# onStep-board-power.net
KiCad netlist of a schematic drawn in Altium Designer
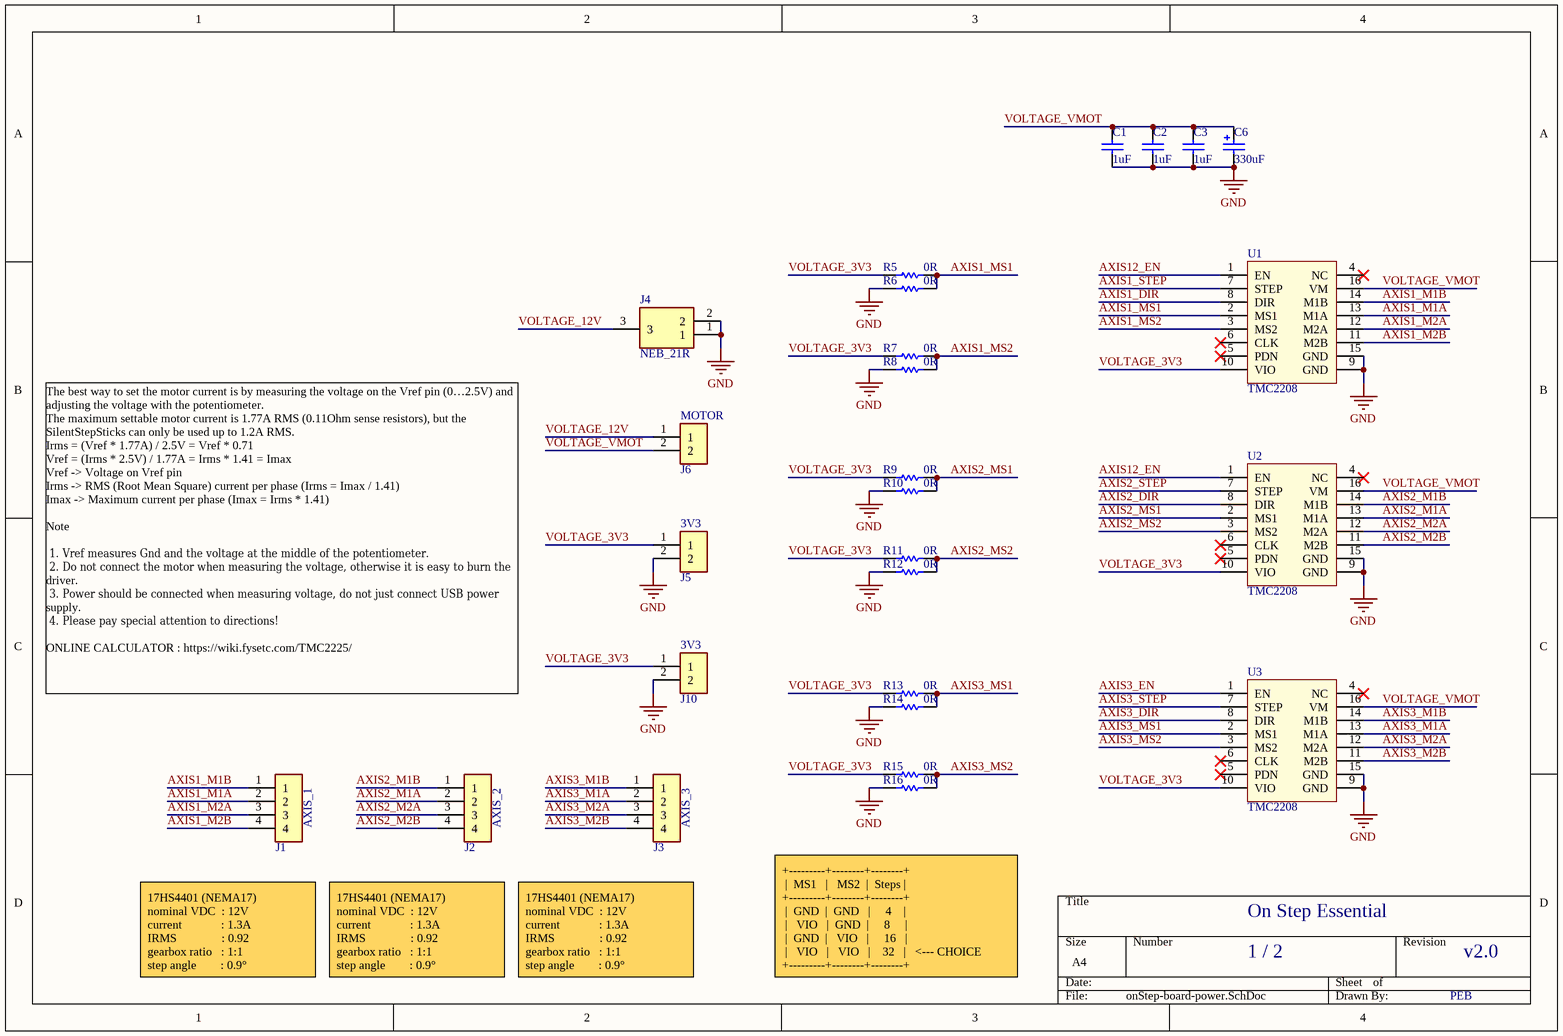
[diagram p0: onStep-board-power.SchDoc]

(export (version "E")
  (design (tool "Eeschema 10.0.6"))
  (components
    (comp (ref "C1")
      (value "1uF")
      (footprint "0805")
      (description "Capacitor")
      (fields (field (name "Comment") "Cap") (field (name "PUBLISHER") "Altium Limited"))
      (libsource (lib "Miscellaneous Devices") (part "Cap"))
    )
    (comp (ref "C2")
      (value "1uF")
      (footprint "0805")
      (description "Capacitor")
      (fields (field (name "Comment") "Cap") (field (name "PUBLISHER") "Altium Limited"))
      (libsource (lib "Miscellaneous Devices") (part "Cap"))
    )
    (comp (ref "C3")
      (value "1uF")
      (footprint "0805")
      (description "Capacitor")
      (fields (field (name "Comment") "Cap") (field (name "PUBLISHER") "Altium Limited"))
      (libsource (lib "Miscellaneous Devices") (part "Cap"))
    )
    (comp (ref "C6")
      (value "330uF")
      (footprint "WCAP-ASLL_8x10.5")
      (description "WCAP-ASLL Aluminum Electrolytic Capacitors, size Ф8x10.5mm, 25V DC, 330uF")
      (fields (field (name "PART NUMBER") "865060453008") (field (name "PUBLISHER") "Wurth Elektronik"))
      (libsource (lib "ALTIUM-WCAP-ASLL-rev17a") (part "865060453008"))
    )
    (comp (ref "J1")
      (value "AXIS_1")
      (footprint "lib_common:B4BXHALFSN")
      (description "Connector")
      (fields (field (name "MANUFACTURER_PART_NUMBER") "B4B-XH-A(LF)(SN)"))
      (libsource (lib "lib_common") (part "B4B-XH-A_LF__SN_"))
    )
    (comp (ref "J2")
      (value "AXIS_2")
      (footprint "lib_common:B4BXHALFSN")
      (description "Connector")
      (fields (field (name "MANUFACTURER_PART_NUMBER") "B4B-XH-A(LF)(SN)"))
      (libsource (lib "lib_common") (part "B4B-XH-A_LF__SN_"))
    )
    (comp (ref "J3")
      (value "AXIS_3")
      (footprint "lib_common:B4BXHALFSN")
      (description "Connector")
      (fields (field (name "MANUFACTURER_PART_NUMBER") "B4B-XH-A(LF)(SN)"))
      (libsource (lib "lib_common") (part "B4B-XH-A_LF__SN_"))
    )
    (comp (ref "J4")
      (value "NEB_21R")
      (footprint "lib_common:NEB21R")
      (description "Connector")
      (fields (field (name "MANUFACTURER_PART_NUMBER") "NEB+21+R"))
      (libsource (lib "lib_common") (part "NEB_21R"))
    )
    (comp (ref "J5")
      (value "3V3")
      (footprint "B2BXHALFSN")
      (description "Connector")
      (fields (field (name "MANUFACTURER_PART_NUMBER") "B2B-XH-A(LF)(SN)"))
      (libsource (lib "lib_common") (part "B2B-XH-A_LF__SN_"))
    )
    (comp (ref "J6")
      (value "MOTOR")
      (footprint "lib_common:B2BXHALFSN")
      (description "Connector")
      (fields (field (name "MANUFACTURER_PART_NUMBER") "B2B-XH-A(LF)(SN)"))
      (libsource (lib "lib_common") (part "B2B-XH-A_LF__SN_"))
    )
    (comp (ref "J10")
      (value "3V3")
      (footprint "B2BXHALFSN")
      (description "Connector")
      (fields (field (name "MANUFACTURER_PART_NUMBER") "B2B-XH-A(LF)(SN)"))
      (libsource (lib "lib_common") (part "B2B-XH-A_LF__SN_"))
    )
    (comp (ref "R5")
      (value "0R")
      (footprint "0805")
      (description "Resistor")
      (fields (field (name "Comment") "Res1") (field (name "PUBLISHER") "Altium Limited"))
      (libsource (lib "Miscellaneous Devices") (part "Res1"))
    )
    (comp (ref "R6")
      (value "0R")
      (footprint "0805")
      (description "Resistor")
      (fields (field (name "Comment") "Res1") (field (name "PUBLISHER") "Altium Limited"))
      (libsource (lib "Miscellaneous Devices") (part "Res1"))
    )
    (comp (ref "R7")
      (value "0R")
      (footprint "0805")
      (description "Resistor")
      (fields (field (name "Comment") "Res1") (field (name "PUBLISHER") "Altium Limited"))
      (libsource (lib "Miscellaneous Devices") (part "Res1"))
    )
    (comp (ref "R8")
      (value "0R")
      (footprint "0805")
      (description "Resistor")
      (fields (field (name "Comment") "Res1") (field (name "PUBLISHER") "Altium Limited"))
      (libsource (lib "Miscellaneous Devices") (part "Res1"))
    )
    (comp (ref "R9")
      (value "0R")
      (footprint "0805")
      (description "Resistor")
      (fields (field (name "Comment") "Res1") (field (name "PUBLISHER") "Altium Limited"))
      (libsource (lib "Miscellaneous Devices") (part "Res1"))
    )
    (comp (ref "R10")
      (value "0R")
      (footprint "0805")
      (description "Resistor")
      (fields (field (name "Comment") "Res1") (field (name "PUBLISHER") "Altium Limited"))
      (libsource (lib "Miscellaneous Devices") (part "Res1"))
    )
    (comp (ref "R11")
      (value "0R")
      (footprint "0805")
      (description "Resistor")
      (fields (field (name "Comment") "Res1") (field (name "PUBLISHER") "Altium Limited"))
      (libsource (lib "Miscellaneous Devices") (part "Res1"))
    )
    (comp (ref "R12")
      (value "0R")
      (footprint "0805")
      (description "Resistor")
      (fields (field (name "Comment") "Res1") (field (name "PUBLISHER") "Altium Limited"))
      (libsource (lib "Miscellaneous Devices") (part "Res1"))
    )
    (comp (ref "R13")
      (value "0R")
      (footprint "0805")
      (description "Resistor")
      (fields (field (name "Comment") "Res1") (field (name "PUBLISHER") "Altium Limited"))
      (libsource (lib "Miscellaneous Devices") (part "Res1"))
    )
    (comp (ref "R14")
      (value "0R")
      (footprint "0805")
      (description "Resistor")
      (fields (field (name "Comment") "Res1") (field (name "PUBLISHER") "Altium Limited"))
      (libsource (lib "Miscellaneous Devices") (part "Res1"))
    )
    (comp (ref "R15")
      (value "0R")
      (footprint "0805")
      (description "Resistor")
      (fields (field (name "Comment") "Res1") (field (name "PUBLISHER") "Altium Limited"))
      (libsource (lib "Miscellaneous Devices") (part "Res1"))
    )
    (comp (ref "R16")
      (value "0R")
      (footprint "0805")
      (description "Resistor")
      (fields (field (name "Comment") "Res1") (field (name "PUBLISHER") "Altium Limited"))
      (libsource (lib "Miscellaneous Devices") (part "Res1"))
    )
    (comp (ref "U1") (value "TMC2208") (footprint "TMC22xx") (libsource (lib "lib_common") (part "TMC2208")))
    (comp (ref "U2") (value "TMC2208") (footprint "TMC22xx") (libsource (lib "lib_common") (part "TMC2208")))
    (comp (ref "U3") (value "TMC2208") (footprint "TMC22xx") (libsource (lib "lib_common") (part "TMC2208")))
  )
  (nets
    (net (code "1") (name "/AXIS1_DIR") (class "Default")
      (node (ref "U1") (pin "8") (pinfunction "DIR_8") (pintype "passive"))
    )
    (net (code "2") (name "/AXIS1_M1A") (class "Default")
      (node (ref "J1") (pin "2") (pinfunction "2_2") (pintype "passive"))
      (node (ref "U1") (pin "13") (pinfunction "M1A_13") (pintype "passive"))
    )
    (net (code "3") (name "/AXIS1_M1B") (class "Default")
      (node (ref "J1") (pin "1") (pinfunction "1_1") (pintype "passive"))
      (node (ref "U1") (pin "14") (pinfunction "M1B_14") (pintype "passive"))
    )
    (net (code "4") (name "/AXIS1_M2A") (class "Default")
      (node (ref "J1") (pin "3") (pinfunction "3_3") (pintype "passive"))
      (node (ref "U1") (pin "12") (pinfunction "M2A_12") (pintype "passive"))
    )
    (net (code "5") (name "/AXIS1_M2B") (class "Default")
      (node (ref "J1") (pin "4") (pinfunction "4_4") (pintype "passive"))
      (node (ref "U1") (pin "11") (pinfunction "M2B_11") (pintype "passive"))
    )
    (net (code "6") (name "/AXIS1_MS1") (class "Default")
      (node (ref "R5") (pin "2") (pinfunction "2_2") (pintype "passive"))
      (node (ref "R6") (pin "2") (pinfunction "2_2") (pintype "passive"))
      (node (ref "U1") (pin "2") (pinfunction "MS1_2") (pintype "passive"))
    )
    (net (code "7") (name "/AXIS1_MS2") (class "Default")
      (node (ref "R7") (pin "2") (pinfunction "2_2") (pintype "passive"))
      (node (ref "R8") (pin "2") (pinfunction "2_2") (pintype "passive"))
      (node (ref "U1") (pin "3") (pinfunction "MS2_3") (pintype "passive"))
    )
    (net (code "8") (name "/AXIS1_STEP") (class "Default")
      (node (ref "U1") (pin "7") (pinfunction "STEP_7") (pintype "passive"))
    )
    (net (code "9") (name "/AXIS2_DIR") (class "Default")
      (node (ref "U2") (pin "8") (pinfunction "DIR_8") (pintype "passive"))
    )
    (net (code "10") (name "/AXIS2_M1A") (class "Default")
      (node (ref "J2") (pin "2") (pinfunction "2_2") (pintype "passive"))
      (node (ref "U2") (pin "13") (pinfunction "M1A_13") (pintype "passive"))
    )
    (net (code "11") (name "/AXIS2_M1B") (class "Default")
      (node (ref "J2") (pin "1") (pinfunction "1_1") (pintype "passive"))
      (node (ref "U2") (pin "14") (pinfunction "M1B_14") (pintype "passive"))
    )
    (net (code "12") (name "/AXIS2_M2A") (class "Default")
      (node (ref "J2") (pin "3") (pinfunction "3_3") (pintype "passive"))
      (node (ref "U2") (pin "12") (pinfunction "M2A_12") (pintype "passive"))
    )
    (net (code "13") (name "/AXIS2_M2B") (class "Default")
      (node (ref "J2") (pin "4") (pinfunction "4_4") (pintype "passive"))
      (node (ref "U2") (pin "11") (pinfunction "M2B_11") (pintype "passive"))
    )
    (net (code "14") (name "/AXIS2_MS1") (class "Default")
      (node (ref "R10") (pin "2") (pinfunction "2_2") (pintype "passive"))
      (node (ref "R9") (pin "2") (pinfunction "2_2") (pintype "passive"))
      (node (ref "U2") (pin "2") (pinfunction "MS1_2") (pintype "passive"))
    )
    (net (code "15") (name "/AXIS2_MS2") (class "Default")
      (node (ref "R11") (pin "2") (pinfunction "2_2") (pintype "passive"))
      (node (ref "R12") (pin "2") (pinfunction "2_2") (pintype "passive"))
      (node (ref "U2") (pin "3") (pinfunction "MS2_3") (pintype "passive"))
    )
    (net (code "16") (name "/AXIS2_STEP") (class "Default")
      (node (ref "U2") (pin "7") (pinfunction "STEP_7") (pintype "passive"))
    )
    (net (code "17") (name "/AXIS3_DIR") (class "Default")
      (node (ref "U3") (pin "8") (pinfunction "DIR_8") (pintype "passive"))
    )
    (net (code "18") (name "/AXIS3_EN") (class "Default")
      (node (ref "U3") (pin "1") (pinfunction "EN_1") (pintype "passive"))
    )
    (net (code "19") (name "/AXIS3_M1A") (class "Default")
      (node (ref "J3") (pin "2") (pinfunction "2_2") (pintype "passive"))
      (node (ref "U3") (pin "13") (pinfunction "M1A_13") (pintype "passive"))
    )
    (net (code "20") (name "/AXIS3_M1B") (class "Default")
      (node (ref "J3") (pin "1") (pinfunction "1_1") (pintype "passive"))
      (node (ref "U3") (pin "14") (pinfunction "M1B_14") (pintype "passive"))
    )
    (net (code "21") (name "/AXIS3_M2A") (class "Default")
      (node (ref "J3") (pin "3") (pinfunction "3_3") (pintype "passive"))
      (node (ref "U3") (pin "12") (pinfunction "M2A_12") (pintype "passive"))
    )
    (net (code "22") (name "/AXIS3_M2B") (class "Default")
      (node (ref "J3") (pin "4") (pinfunction "4_4") (pintype "passive"))
      (node (ref "U3") (pin "11") (pinfunction "M2B_11") (pintype "passive"))
    )
    (net (code "23") (name "/AXIS3_MS1") (class "Default")
      (node (ref "R13") (pin "2") (pinfunction "2_2") (pintype "passive"))
      (node (ref "R14") (pin "2") (pinfunction "2_2") (pintype "passive"))
      (node (ref "U3") (pin "2") (pinfunction "MS1_2") (pintype "passive"))
    )
    (net (code "24") (name "/AXIS3_MS2") (class "Default")
      (node (ref "R15") (pin "2") (pinfunction "2_2") (pintype "passive"))
      (node (ref "R16") (pin "2") (pinfunction "2_2") (pintype "passive"))
      (node (ref "U3") (pin "3") (pinfunction "MS2_3") (pintype "passive"))
    )
    (net (code "25") (name "/AXIS3_STEP") (class "Default")
      (node (ref "U3") (pin "7") (pinfunction "STEP_7") (pintype "passive"))
    )
    (net (code "26") (name "/AXIS12_EN") (class "Default")
      (node (ref "U1") (pin "1") (pinfunction "EN_1") (pintype "passive"))
      (node (ref "U2") (pin "1") (pinfunction "EN_1") (pintype "passive"))
    )
    (net (code "27") (name "/VOLTAGE_3V3") (class "Default")
      (node (ref "J10") (pin "1") (pinfunction "1_1") (pintype "passive"))
      (node (ref "J5") (pin "1") (pinfunction "1_1") (pintype "passive"))
      (node (ref "R11") (pin "1") (pinfunction "1_1") (pintype "passive"))
      (node (ref "R13") (pin "1") (pinfunction "1_1") (pintype "passive"))
      (node (ref "R15") (pin "1") (pinfunction "1_1") (pintype "passive"))
      (node (ref "R5") (pin "1") (pinfunction "1_1") (pintype "passive"))
      (node (ref "R7") (pin "1") (pinfunction "1_1") (pintype "passive"))
      (node (ref "R9") (pin "1") (pinfunction "1_1") (pintype "passive"))
      (node (ref "U1") (pin "10") (pinfunction "VIO_10") (pintype "passive"))
      (node (ref "U2") (pin "10") (pinfunction "VIO_10") (pintype "passive"))
      (node (ref "U3") (pin "10") (pinfunction "VIO_10") (pintype "passive"))
    )
    (net (code "28") (name "/VOLTAGE_12V") (class "Default")
      (node (ref "J4") (pin "3") (pinfunction "3_3") (pintype "passive"))
      (node (ref "J6") (pin "1") (pinfunction "1_1") (pintype "passive"))
    )
    (net (code "29") (name "/VOLTAGE_VMOT") (class "Default")
      (node (ref "C1") (pin "2") (pinfunction "2_2") (pintype "passive"))
      (node (ref "C2") (pin "2") (pinfunction "2_2") (pintype "passive"))
      (node (ref "C3") (pin "2") (pinfunction "2_2") (pintype "passive"))
      (node (ref "C6") (pin "1") (pinfunction "P_1") (pintype "passive"))
      (node (ref "J6") (pin "2") (pinfunction "2_2") (pintype "passive"))
      (node (ref "U1") (pin "16") (pinfunction "VM_16") (pintype "passive"))
      (node (ref "U2") (pin "16") (pinfunction "VM_16") (pintype "passive"))
      (node (ref "U3") (pin "16") (pinfunction "VM_16") (pintype "passive"))
    )
    (net (code "30") (name "GND") (class "Default")
      (node (ref "C1") (pin "1") (pinfunction "1_1") (pintype "passive"))
      (node (ref "C2") (pin "1") (pinfunction "1_1") (pintype "passive"))
      (node (ref "C3") (pin "1") (pinfunction "1_1") (pintype "passive"))
      (node (ref "C6") (pin "2") (pinfunction "N_2") (pintype "passive"))
      (node (ref "J10") (pin "2") (pinfunction "2_2") (pintype "passive"))
      (node (ref "J4") (pin "1") (pinfunction "1_1") (pintype "passive"))
      (node (ref "J4") (pin "2") (pinfunction "2_2") (pintype "passive"))
      (node (ref "J5") (pin "2") (pinfunction "2_2") (pintype "passive"))
      (node (ref "R10") (pin "1") (pinfunction "1_1") (pintype "passive"))
      (node (ref "R12") (pin "1") (pinfunction "1_1") (pintype "passive"))
      (node (ref "R14") (pin "1") (pinfunction "1_1") (pintype "passive"))
      (node (ref "R16") (pin "1") (pinfunction "1_1") (pintype "passive"))
      (node (ref "R6") (pin "1") (pinfunction "1_1") (pintype "passive"))
      (node (ref "R8") (pin "1") (pinfunction "1_1") (pintype "passive"))
      (node (ref "U1") (pin "15") (pinfunction "GND_15") (pintype "passive"))
      (node (ref "U1") (pin "9") (pinfunction "GND_9") (pintype "passive"))
      (node (ref "U2") (pin "15") (pinfunction "GND_15") (pintype "passive"))
      (node (ref "U2") (pin "9") (pinfunction "GND_9") (pintype "passive"))
      (node (ref "U3") (pin "15") (pinfunction "GND_15") (pintype "passive"))
      (node (ref "U3") (pin "9") (pinfunction "GND_9") (pintype "passive"))
    )
    (net (code "31") (name "unconnected-(U1-CLK-Pad6)") (class "Default")
      (node (ref "U1") (pin "6") (pinfunction "CLK_6") (pintype "passive+no_connect"))
    )
    (net (code "32") (name "unconnected-(U1-NC-Pad4)") (class "Default")
      (node (ref "U1") (pin "4") (pinfunction "NC_4") (pintype "passive+no_connect"))
    )
    (net (code "33") (name "unconnected-(U1-PDN-Pad5)") (class "Default")
      (node (ref "U1") (pin "5") (pinfunction "PDN_5") (pintype "passive+no_connect"))
    )
    (net (code "34") (name "unconnected-(U2-CLK-Pad6)") (class "Default")
      (node (ref "U2") (pin "6") (pinfunction "CLK_6") (pintype "passive+no_connect"))
    )
    (net (code "35") (name "unconnected-(U2-NC-Pad4)") (class "Default")
      (node (ref "U2") (pin "4") (pinfunction "NC_4") (pintype "passive+no_connect"))
    )
    (net (code "36") (name "unconnected-(U2-PDN-Pad5)") (class "Default")
      (node (ref "U2") (pin "5") (pinfunction "PDN_5") (pintype "passive+no_connect"))
    )
    (net (code "37") (name "unconnected-(U3-CLK-Pad6)") (class "Default")
      (node (ref "U3") (pin "6") (pinfunction "CLK_6") (pintype "passive+no_connect"))
    )
    (net (code "38") (name "unconnected-(U3-NC-Pad4)") (class "Default")
      (node (ref "U3") (pin "4") (pinfunction "NC_4") (pintype "passive+no_connect"))
    )
    (net (code "39") (name "unconnected-(U3-PDN-Pad5)") (class "Default")
      (node (ref "U3") (pin "5") (pinfunction "PDN_5") (pintype "passive+no_connect"))
    )
  )
)
